# T3HornetV2.net
KiCad netlist of a schematic drawn in EAGLE
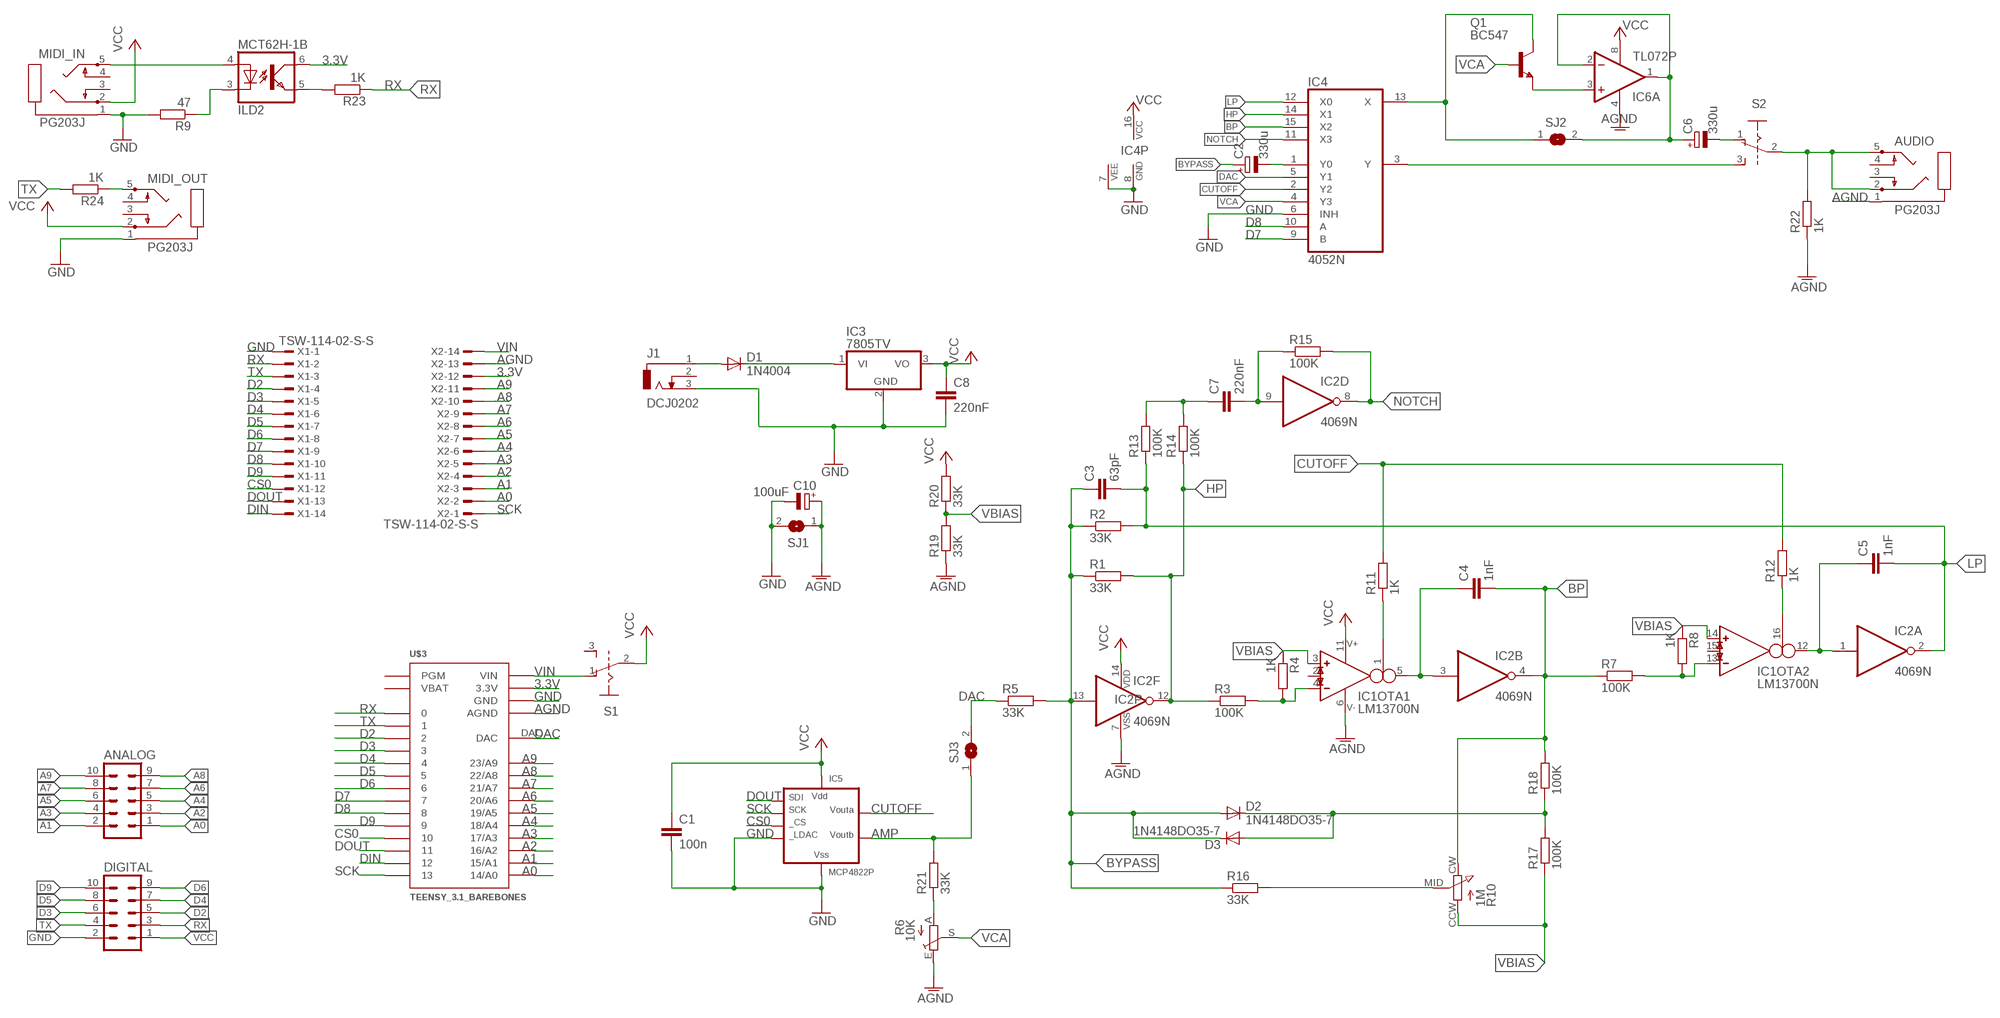
[diagram p0: schematic, sheet 1]

(export (version "E")
  (design (tool "Eeschema 10.0.6"))
  (components
    (comp (ref "ANALOG")
      (value "ML10")
      (footprint "eagle-import:ML10")
      (libsource (lib "eagle-import") (part "ML10"))
    )
    (comp (ref "AUDIO")
      (value "PG203J")
      (footprint "eagle-import:PG203J")
      (libsource (lib "eagle-import") (part "PG203J"))
    )
    (comp (ref "C1")
      (value "100n")
      (footprint "eagle-import:C050-030X075")
      (libsource (lib "eagle-import") (part "C-EU050-030X075"))
    )
    (comp (ref "C2")
      (value "330u")
      (footprint "eagle-import:E2,5-7")
      (libsource (lib "eagle-import") (part "CPOL-EUE2.5-7"))
    )
    (comp (ref "C3")
      (value "63pF")
      (footprint "eagle-import:C025-024X044")
      (libsource (lib "eagle-import") (part "C-EU025-024X044"))
    )
    (comp (ref "C4")
      (value "1nF")
      (footprint "eagle-import:C025-024X044")
      (libsource (lib "eagle-import") (part "C-EU025-024X044"))
    )
    (comp (ref "C5")
      (value "1nF")
      (footprint "eagle-import:C025-024X044")
      (libsource (lib "eagle-import") (part "C-EU025-024X044"))
    )
    (comp (ref "C6")
      (value "330u")
      (footprint "eagle-import:E2,5-7")
      (libsource (lib "eagle-import") (part "CPOL-EUE2.5-7"))
    )
    (comp (ref "C7")
      (value "220nF")
      (footprint "eagle-import:C050-030X075")
      (libsource (lib "eagle-import") (part "C-EU050-030X075"))
    )
    (comp (ref "C8")
      (value "220nF")
      (footprint "eagle-import:C050-030X075")
      (libsource (lib "eagle-import") (part "C-EU050-030X075"))
    )
    (comp (ref "C10")
      (value "100uF")
      (footprint "eagle-import:E2,5-6")
      (libsource (lib "eagle-import") (part "CPOL-EUE2.5-6"))
    )
    (comp (ref "D1")
      (value "1N4004")
      (footprint "eagle-import:DO41-10")
      (libsource (lib "eagle-import") (part "1N4004"))
    )
    (comp (ref "D2")
      (value "1N4148DO35-7")
      (footprint "eagle-import:DO35-7")
      (libsource (lib "eagle-import") (part "1N4148DO35-7"))
    )
    (comp (ref "D3")
      (value "1N4148DO35-7")
      (footprint "eagle-import:DO35-7")
      (libsource (lib "eagle-import") (part "1N4148DO35-7"))
    )
    (comp (ref "DIGITAL")
      (value "ML10")
      (footprint "eagle-import:ML10")
      (libsource (lib "eagle-import") (part "ML10"))
    )
    (comp (ref "IC1")
      (value "LM13700N")
      (footprint "eagle-import:DIL16")
      (libsource (lib "eagle-import") (part "LM13700N"))
    )
    (comp (ref "IC2")
      (value "4069N")
      (footprint "eagle-import:DIL14")
      (libsource (lib "eagle-import") (part "4069N"))
    )
    (comp (ref "IC3")
      (value "7805TV")
      (footprint "eagle-import:TO220V")
      (libsource (lib "eagle-import") (part "78TV05"))
    )
    (comp (ref "IC4")
      (value "4052N")
      (footprint "eagle-import:DIL16")
      (libsource (lib "eagle-import") (part "4052N"))
    )
    (comp (ref "IC5")
      (value "MCP4822P")
      (footprint "eagle-import:DIL8")
      (libsource (lib "eagle-import") (part "MCP4822P"))
    )
    (comp (ref "IC6")
      (value "TL072P")
      (footprint "eagle-import:DIL08")
      (libsource (lib "eagle-import") (part "TL072P"))
    )
    (comp (ref "J1")
      (value "DCJ0202")
      (footprint "eagle-import:DCJ0202")
      (libsource (lib "eagle-import") (part "DCJ0202"))
    )
    (comp (ref "MCT62H-1")
      (value "ILD2")
      (footprint "eagle-import:DIL08")
      (libsource (lib "eagle-import") (part "ILD2"))
    )
    (comp (ref "MIDI_IN")
      (value "PG203J")
      (footprint "eagle-import:PG203J")
      (libsource (lib "eagle-import") (part "PG203J"))
    )
    (comp (ref "MIDI_OUT")
      (value "PG203J")
      (footprint "eagle-import:PG203J")
      (libsource (lib "eagle-import") (part "PG203J"))
    )
    (comp (ref "Q1")
      (value "BC547")
      (footprint "eagle-import:TO92")
      (libsource (lib "eagle-import") (part "BC547"))
    )
    (comp (ref "R1")
      (value "33K")
      (footprint "eagle-import:0207_7")
      (libsource (lib "eagle-import") (part "R-EU_0207/7"))
    )
    (comp (ref "R2")
      (value "33K")
      (footprint "eagle-import:0207_7")
      (libsource (lib "eagle-import") (part "R-EU_0207/7"))
    )
    (comp (ref "R3")
      (value "100K")
      (footprint "eagle-import:0207_7")
      (libsource (lib "eagle-import") (part "R-EU_0207/7"))
    )
    (comp (ref "R4")
      (value "1K")
      (footprint "eagle-import:0207_7")
      (libsource (lib "eagle-import") (part "R-EU_0207/7"))
    )
    (comp (ref "R5")
      (value "33K")
      (footprint "eagle-import:0207_7")
      (libsource (lib "eagle-import") (part "R-EU_0207/7"))
    )
    (comp (ref "R6")
      (value "10K")
      (footprint "eagle-import:CA9V")
      (libsource (lib "eagle-import") (part "TRIM_EU-CA9V"))
    )
    (comp (ref "R7")
      (value "100K")
      (footprint "eagle-import:0207_7")
      (libsource (lib "eagle-import") (part "R-EU_0207/7"))
    )
    (comp (ref "R8")
      (value "1K")
      (footprint "eagle-import:0207_7")
      (libsource (lib "eagle-import") (part "R-EU_0207/7"))
    )
    (comp (ref "R9")
      (value "47")
      (footprint "eagle-import:0207_7")
      (libsource (lib "eagle-import") (part "R-EU_0207/7"))
    )
    (comp (ref "R10")
      (value "1M")
      (footprint "eagle-import:P120PK")
      (libsource (lib "eagle-import") (part "P120PK"))
    )
    (comp (ref "R11")
      (value "1K")
      (footprint "eagle-import:0207_7")
      (libsource (lib "eagle-import") (part "R-EU_0207/7"))
    )
    (comp (ref "R12")
      (value "1K")
      (footprint "eagle-import:0207_7")
      (libsource (lib "eagle-import") (part "R-EU_0207/7"))
    )
    (comp (ref "R13")
      (value "100K")
      (footprint "eagle-import:0207_7")
      (libsource (lib "eagle-import") (part "R-EU_0207/7"))
    )
    (comp (ref "R14")
      (value "100K")
      (footprint "eagle-import:0207_7")
      (libsource (lib "eagle-import") (part "R-EU_0207/7"))
    )
    (comp (ref "R15")
      (value "100K")
      (footprint "eagle-import:0207_7")
      (libsource (lib "eagle-import") (part "R-EU_0207/7"))
    )
    (comp (ref "R16")
      (value "33K")
      (footprint "eagle-import:0207_7")
      (libsource (lib "eagle-import") (part "R-EU_0207/7"))
    )
    (comp (ref "R17")
      (value "100K")
      (footprint "eagle-import:0207_7")
      (libsource (lib "eagle-import") (part "R-EU_0207/7"))
    )
    (comp (ref "R18")
      (value "100K")
      (footprint "eagle-import:0207_7")
      (libsource (lib "eagle-import") (part "R-EU_0207/7"))
    )
    (comp (ref "R19")
      (value "33K")
      (footprint "eagle-import:0207_7")
      (libsource (lib "eagle-import") (part "R-EU_0207/7"))
    )
    (comp (ref "R20")
      (value "33K")
      (footprint "eagle-import:0207_7")
      (libsource (lib "eagle-import") (part "R-EU_0207/7"))
    )
    (comp (ref "R21")
      (value "33K")
      (footprint "eagle-import:0207_7")
      (libsource (lib "eagle-import") (part "R-EU_0207/7"))
    )
    (comp (ref "R22")
      (value "1K")
      (footprint "eagle-import:0207_7")
      (libsource (lib "eagle-import") (part "R-EU_0207/7"))
    )
    (comp (ref "R23")
      (value "1K")
      (footprint "eagle-import:0207_7")
      (libsource (lib "eagle-import") (part "R-EU_0207/7"))
    )
    (comp (ref "R24")
      (value "1K")
      (footprint "eagle-import:0207_7")
      (libsource (lib "eagle-import") (part "R-EU_0207/7"))
    )
    (comp (ref "S1")
      (value "EG1218")
      (footprint "eagle-import:GF-126-0159")
      (libsource (lib "eagle-import") (part "EG1218"))
    )
    (comp (ref "S2")
      (value "EG1218")
      (footprint "eagle-import:GF-126-0159")
      (libsource (lib "eagle-import") (part "EG1218"))
    )
    (comp (ref "SJ1") (value "SJ") (footprint "eagle-import:SJ") (libsource (lib "eagle-import") (part "SJ")))
    (comp (ref "SJ2") (value "SJ") (footprint "eagle-import:SJ") (libsource (lib "eagle-import") (part "SJ")))
    (comp (ref "SJ3") (value "SJ") (footprint "eagle-import:SJ") (libsource (lib "eagle-import") (part "SJ")))
    (comp (ref "U$3")
      (value "TEENSY_3.1_BAREBONES")
      (footprint "eagle-import:TEENSY_3.1_BAREBONES")
      (libsource (lib "eagle-import") (part "TEENSY_3.1_BAREBONES"))
    )
    (comp (ref "X1")
      (value "TSW-114-02-S-S")
      (footprint "eagle-import:TSW-114-02-S-S")
      (libsource (lib "eagle-import") (part "TSW-114-02-S-S"))
    )
    (comp (ref "X2")
      (value "TSW-114-02-S-S")
      (footprint "eagle-import:TSW-114-02-S-S")
      (libsource (lib "eagle-import") (part "TSW-114-02-S-S"))
    )
  )
  (nets
    (net (code "1") (name "/3.3V") (class "Default")
      (node (ref "MCT62H-1") (pin "6") (pinfunction "COL_6") (pintype "passive"))
      (node (ref "U$3") (pin "3.3V1") (pinfunction "3.3V_3.3V1") (pintype "power_in"))
      (node (ref "U$3") (pin "3.3V2") (pinfunction "3.3V_3.3V2") (pintype "power_in"))
      (node (ref "X2") (pin "12") (pinfunction "1_12") (pintype "passive"))
    )
    (net (code "2") (name "/AMP") (class "Default")
      (node (ref "IC5") (pin "6") (pinfunction "VOUTB_6") (pintype "output"))
      (node (ref "R21") (pin "2") (pinfunction "2_2") (pintype "passive"))
      (node (ref "SJ3") (pin "1") (pinfunction "1_1") (pintype "passive"))
    )
    (net (code "3") (name "/CS0") (class "Default")
      (node (ref "IC5") (pin "2") (pinfunction "CS_2") (pintype "input"))
      (node (ref "U$3") (pin "10") (pinfunction "10_10") (pintype "bidirectional"))
      (node (ref "X1") (pin "12") (pinfunction "1_12") (pintype "passive"))
    )
    (net (code "4") (name "/D7") (class "Default")
      (node (ref "IC4") (pin "9") (pinfunction "B_9") (pintype "input"))
      (node (ref "U$3") (pin "7") (pinfunction "7_7") (pintype "bidirectional"))
      (node (ref "X1") (pin "9") (pinfunction "1_9") (pintype "passive"))
    )
    (net (code "5") (name "/D8") (class "Default")
      (node (ref "IC4") (pin "10") (pinfunction "A_10") (pintype "input"))
      (node (ref "U$3") (pin "8") (pinfunction "8_8") (pintype "bidirectional"))
      (node (ref "X1") (pin "10") (pinfunction "1_10") (pintype "passive"))
    )
    (net (code "6") (name "/DIN") (class "Default")
      (node (ref "U$3") (pin "12") (pinfunction "12_12") (pintype "bidirectional"))
      (node (ref "X1") (pin "14") (pinfunction "1_14") (pintype "passive"))
    )
    (net (code "7") (name "/DOUT") (class "Default")
      (node (ref "IC5") (pin "4") (pinfunction "SDI_4") (pintype "input"))
      (node (ref "U$3") (pin "11") (pinfunction "11_11") (pintype "bidirectional"))
      (node (ref "X1") (pin "13") (pinfunction "1_13") (pintype "passive"))
    )
    (net (code "8") (name "/SCK") (class "Default")
      (node (ref "IC5") (pin "3") (pinfunction "SCK_3") (pintype "input"))
      (node (ref "U$3") (pin "13") (pinfunction "13_13") (pintype "bidirectional"))
      (node (ref "X2") (pin "1") (pinfunction "1_1") (pintype "passive"))
    )
    (net (code "9") (name "/VBAT") (class "Default")
      (node (ref "U$3") (pin "VBAT") (pinfunction "VBAT_VBAT") (pintype "power_in"))
    )
    (net (code "10") (name "/VIN") (class "Default")
      (node (ref "S1") (pin "1") (pinfunction "1_1") (pintype "passive"))
      (node (ref "U$3") (pin "VIN") (pinfunction "VIN_VIN") (pintype "power_in"))
      (node (ref "X2") (pin "14") (pinfunction "1_14") (pintype "passive"))
    )
    (net (code "11") (name "A0") (class "Default")
      (node (ref "ANALOG") (pin "1") (pinfunction "1_1") (pintype "passive"))
      (node (ref "U$3") (pin "14/A0") (pinfunction "14/A0_14/A0") (pintype "bidirectional"))
      (node (ref "X2") (pin "2") (pinfunction "1_2") (pintype "passive"))
    )
    (net (code "12") (name "A1") (class "Default")
      (node (ref "ANALOG") (pin "2") (pinfunction "2_2") (pintype "passive"))
      (node (ref "U$3") (pin "15/A1") (pinfunction "15/A1_15/A1") (pintype "bidirectional"))
      (node (ref "X2") (pin "3") (pinfunction "1_3") (pintype "passive"))
    )
    (net (code "13") (name "A2") (class "Default")
      (node (ref "ANALOG") (pin "3") (pinfunction "3_3") (pintype "passive"))
      (node (ref "U$3") (pin "16/A2") (pinfunction "16/A2_16/A2") (pintype "bidirectional"))
      (node (ref "X2") (pin "4") (pinfunction "1_4") (pintype "passive"))
    )
    (net (code "14") (name "A3") (class "Default")
      (node (ref "ANALOG") (pin "4") (pinfunction "4_4") (pintype "passive"))
      (node (ref "U$3") (pin "17/A3") (pinfunction "17/A3_17/A3") (pintype "bidirectional"))
      (node (ref "X2") (pin "5") (pinfunction "1_5") (pintype "passive"))
    )
    (net (code "15") (name "A4") (class "Default")
      (node (ref "ANALOG") (pin "5") (pinfunction "5_5") (pintype "passive"))
      (node (ref "U$3") (pin "18/A4") (pinfunction "18/A4_18/A4") (pintype "bidirectional"))
      (node (ref "X2") (pin "6") (pinfunction "1_6") (pintype "passive"))
    )
    (net (code "16") (name "A5") (class "Default")
      (node (ref "ANALOG") (pin "6") (pinfunction "6_6") (pintype "passive"))
      (node (ref "U$3") (pin "19/A5") (pinfunction "19/A5_19/A5") (pintype "bidirectional"))
      (node (ref "X2") (pin "7") (pinfunction "1_7") (pintype "passive"))
    )
    (net (code "17") (name "A6") (class "Default")
      (node (ref "ANALOG") (pin "7") (pinfunction "7_7") (pintype "passive"))
      (node (ref "U$3") (pin "20/A6") (pinfunction "20/A6_20/A6") (pintype "bidirectional"))
      (node (ref "X2") (pin "8") (pinfunction "1_8") (pintype "passive"))
    )
    (net (code "18") (name "A7") (class "Default")
      (node (ref "ANALOG") (pin "8") (pinfunction "8_8") (pintype "passive"))
      (node (ref "U$3") (pin "21/A7") (pinfunction "21/A7_21/A7") (pintype "bidirectional"))
      (node (ref "X2") (pin "9") (pinfunction "1_9") (pintype "passive"))
    )
    (net (code "19") (name "A8") (class "Default")
      (node (ref "ANALOG") (pin "9") (pinfunction "9_9") (pintype "passive"))
      (node (ref "U$3") (pin "22/A8") (pinfunction "22/A8_22/A8") (pintype "bidirectional"))
      (node (ref "X2") (pin "10") (pinfunction "1_10") (pintype "passive"))
    )
    (net (code "20") (name "A9") (class "Default")
      (node (ref "ANALOG") (pin "10") (pinfunction "10_10") (pintype "passive"))
      (node (ref "U$3") (pin "23/A9") (pinfunction "23/A9_23/A9") (pintype "bidirectional"))
      (node (ref "X2") (pin "11") (pinfunction "1_11") (pintype "passive"))
    )
    (net (code "21") (name "AGND") (class "Default")
      (node (ref "AUDIO") (pin "1") (pinfunction "1_1") (pintype "passive"))
      (node (ref "C10") (pin "+") (pinfunction "+_+") (pintype "passive"))
      (node (ref "IC1") (pin "6") (pinfunction "V-_6") (pintype "power_in"))
      (node (ref "IC2") (pin "7") (pinfunction "VSS_7") (pintype "power_in"))
      (node (ref "IC6") (pin "4") (pinfunction "V-_4") (pintype "power_in"))
      (node (ref "R19") (pin "1") (pinfunction "1_1") (pintype "passive"))
      (node (ref "R22") (pin "1") (pinfunction "1_1") (pintype "passive"))
      (node (ref "R6") (pin "E") (pinfunction "E_E") (pintype "passive"))
      (node (ref "SJ1") (pin "1") (pinfunction "1_1") (pintype "passive"))
      (node (ref "U$3") (pin "AGND") (pinfunction "AGND_AGND") (pintype "power_in"))
      (node (ref "X2") (pin "13") (pinfunction "1_13") (pintype "passive"))
    )
    (net (code "22") (name "BP") (class "Default")
      (node (ref "C4") (pin "2") (pinfunction "2_2") (pintype "passive"))
      (node (ref "IC2") (pin "4") (pinfunction "O_4") (pintype "output"))
      (node (ref "IC4") (pin "15") (pinfunction "X2_15") (pintype "bidirectional"))
      (node (ref "R10") (pin "CW") (pinfunction "CW_CW") (pintype "passive"))
      (node (ref "R18") (pin "2") (pinfunction "2_2") (pintype "passive"))
      (node (ref "R7") (pin "1") (pinfunction "1_1") (pintype "passive"))
    )
    (net (code "23") (name "BYPASS") (class "Default")
      (node (ref "C2") (pin "+") (pinfunction "+_+") (pintype "passive"))
      (node (ref "C3") (pin "1") (pinfunction "1_1") (pintype "passive"))
      (node (ref "D2") (pin "A") (pinfunction "A_A") (pintype "passive"))
      (node (ref "D3") (pin "C") (pinfunction "C_C") (pintype "passive"))
      (node (ref "IC2") (pin "13") (pinfunction "I_13") (pintype "input"))
      (node (ref "R1") (pin "1") (pinfunction "1_1") (pintype "passive"))
      (node (ref "R16") (pin "1") (pinfunction "1_1") (pintype "passive"))
      (node (ref "R2") (pin "1") (pinfunction "1_1") (pintype "passive"))
      (node (ref "R5") (pin "2") (pinfunction "2_2") (pintype "passive"))
    )
    (net (code "24") (name "CUTOFF") (class "Default")
      (node (ref "IC4") (pin "2") (pinfunction "Y2_2") (pintype "bidirectional"))
      (node (ref "IC5") (pin "8") (pinfunction "VOUTA_8") (pintype "output"))
      (node (ref "R11") (pin "2") (pinfunction "2_2") (pintype "passive"))
      (node (ref "R12") (pin "2") (pinfunction "2_2") (pintype "passive"))
    )
    (net (code "25") (name "D2") (class "Default")
      (node (ref "DIGITAL") (pin "5") (pinfunction "5_5") (pintype "passive"))
      (node (ref "U$3") (pin "2") (pinfunction "2_2") (pintype "bidirectional"))
      (node (ref "X1") (pin "4") (pinfunction "1_4") (pintype "passive"))
    )
    (net (code "26") (name "D3") (class "Default")
      (node (ref "DIGITAL") (pin "6") (pinfunction "6_6") (pintype "passive"))
      (node (ref "U$3") (pin "3") (pinfunction "3_3") (pintype "bidirectional"))
      (node (ref "X1") (pin "5") (pinfunction "1_5") (pintype "passive"))
    )
    (net (code "27") (name "D4") (class "Default")
      (node (ref "DIGITAL") (pin "7") (pinfunction "7_7") (pintype "passive"))
      (node (ref "U$3") (pin "4") (pinfunction "4_4") (pintype "bidirectional"))
      (node (ref "X1") (pin "6") (pinfunction "1_6") (pintype "passive"))
    )
    (net (code "28") (name "D5") (class "Default")
      (node (ref "DIGITAL") (pin "8") (pinfunction "8_8") (pintype "passive"))
      (node (ref "U$3") (pin "5") (pinfunction "5_5") (pintype "bidirectional"))
      (node (ref "X1") (pin "7") (pinfunction "1_7") (pintype "passive"))
    )
    (net (code "29") (name "D6") (class "Default")
      (node (ref "DIGITAL") (pin "9") (pinfunction "9_9") (pintype "passive"))
      (node (ref "U$3") (pin "6") (pinfunction "6_6") (pintype "bidirectional"))
      (node (ref "X1") (pin "8") (pinfunction "1_8") (pintype "passive"))
    )
    (net (code "30") (name "D9") (class "Default")
      (node (ref "DIGITAL") (pin "10") (pinfunction "10_10") (pintype "passive"))
      (node (ref "U$3") (pin "9") (pinfunction "9_9") (pintype "bidirectional"))
      (node (ref "X1") (pin "11") (pinfunction "1_11") (pintype "passive"))
    )
    (net (code "31") (name "DAC") (class "Default")
      (node (ref "IC4") (pin "5") (pinfunction "Y1_5") (pintype "bidirectional"))
      (node (ref "R5") (pin "1") (pinfunction "1_1") (pintype "passive"))
      (node (ref "SJ3") (pin "2") (pinfunction "2_2") (pintype "passive"))
      (node (ref "U$3") (pin "DAC") (pinfunction "DAC_DAC") (pintype "bidirectional"))
    )
    (net (code "32") (name "GND") (class "Default")
      (node (ref "C1") (pin "2") (pinfunction "2_2") (pintype "passive"))
      (node (ref "C10") (pin "-") (pinfunction "-_-") (pintype "passive"))
      (node (ref "C8") (pin "2") (pinfunction "2_2") (pintype "passive"))
      (node (ref "DIGITAL") (pin "2") (pinfunction "2_2") (pintype "passive"))
      (node (ref "IC3") (pin "2") (pinfunction "GND_2") (pintype "passive"))
      (node (ref "IC4") (pin "6") (pinfunction "INH_6") (pintype "input"))
      (node (ref "IC4") (pin "7") (pinfunction "VEE_7") (pintype "power_in"))
      (node (ref "IC4") (pin "8") (pinfunction "GND_8") (pintype "power_in"))
      (node (ref "IC5") (pin "5") (pinfunction "LDAC_5") (pintype "input"))
      (node (ref "IC5") (pin "7") (pinfunction "VSS_7") (pintype "power_in"))
      (node (ref "J1") (pin "3") (pinfunction "3_3") (pintype "passive"))
      (node (ref "MIDI_IN") (pin "1") (pinfunction "1_1") (pintype "passive"))
      (node (ref "MIDI_OUT") (pin "1") (pinfunction "1_1") (pintype "passive"))
      (node (ref "R9") (pin "2") (pinfunction "2_2") (pintype "passive"))
      (node (ref "SJ1") (pin "2") (pinfunction "2_2") (pintype "passive"))
      (node (ref "U$3") (pin "GND1") (pinfunction "GND_GND1") (pintype "power_in"))
      (node (ref "U$3") (pin "GND2") (pinfunction "GND_GND2") (pintype "power_in"))
      (node (ref "X1") (pin "1") (pinfunction "1_1") (pintype "passive"))
    )
    (net (code "33") (name "HP") (class "Default")
      (node (ref "IC2") (pin "12") (pinfunction "O_12") (pintype "output"))
      (node (ref "IC4") (pin "14") (pinfunction "X1_14") (pintype "bidirectional"))
      (node (ref "R1") (pin "2") (pinfunction "2_2") (pintype "passive"))
      (node (ref "R14") (pin "1") (pinfunction "1_1") (pintype "passive"))
      (node (ref "R3") (pin "1") (pinfunction "1_1") (pintype "passive"))
    )
    (net (code "34") (name "LP") (class "Default")
      (node (ref "C3") (pin "2") (pinfunction "2_2") (pintype "passive"))
      (node (ref "C5") (pin "2") (pinfunction "2_2") (pintype "passive"))
      (node (ref "IC2") (pin "2") (pinfunction "O_2") (pintype "output"))
      (node (ref "IC4") (pin "12") (pinfunction "X0_12") (pintype "bidirectional"))
      (node (ref "R13") (pin "1") (pinfunction "1_1") (pintype "passive"))
      (node (ref "R2") (pin "2") (pinfunction "2_2") (pintype "passive"))
    )
    (net (code "35") (name "NOTCH") (class "Default")
      (node (ref "IC2") (pin "8") (pinfunction "O_8") (pintype "output"))
      (node (ref "IC4") (pin "11") (pinfunction "X3_11") (pintype "bidirectional"))
      (node (ref "R15") (pin "2") (pinfunction "2_2") (pintype "passive"))
    )
    (net (code "36") (name "Net-(C6-Pad-)") (class "Default")
      (node (ref "C6") (pin "-") (pinfunction "-_-") (pintype "passive"))
      (node (ref "S2") (pin "1") (pinfunction "1_1") (pintype "passive"))
    )
    (net (code "37") (name "Net-(C7-Pad1)") (class "Default")
      (node (ref "C7") (pin "1") (pinfunction "1_1") (pintype "passive"))
      (node (ref "R13") (pin "2") (pinfunction "2_2") (pintype "passive"))
      (node (ref "R14") (pin "2") (pinfunction "2_2") (pintype "passive"))
    )
    (net (code "38") (name "Net-(D1-PadA)") (class "Default")
      (node (ref "D1") (pin "A") (pinfunction "A_A") (pintype "passive"))
      (node (ref "J1") (pin "1") (pinfunction "1_1") (pintype "passive"))
    )
    (net (code "39") (name "Net-(D2-PadC)") (class "Default")
      (node (ref "D2") (pin "C") (pinfunction "C_C") (pintype "passive"))
      (node (ref "D3") (pin "A") (pinfunction "A_A") (pintype "passive"))
      (node (ref "R17") (pin "2") (pinfunction "2_2") (pintype "passive"))
      (node (ref "R18") (pin "1") (pinfunction "1_1") (pintype "passive"))
    )
    (net (code "40") (name "Net-(IC1C-IN_N)") (class "Default")
      (node (ref "IC1") (pin "4") (pinfunction "IN_N_4") (pintype "input"))
      (node (ref "R3") (pin "2") (pinfunction "2_2") (pintype "passive"))
      (node (ref "R4") (pin "2") (pinfunction "2_2") (pintype "passive"))
    )
    (net (code "41") (name "Net-(IC1C-I_BIAS)") (class "Default")
      (node (ref "IC1") (pin "1") (pinfunction "I_BIAS_1") (pintype "input"))
      (node (ref "R11") (pin "1") (pinfunction "1_1") (pintype "passive"))
    )
    (net (code "42") (name "Net-(IC1C-OUT)") (class "Default")
      (node (ref "C4") (pin "1") (pinfunction "1_1") (pintype "passive"))
      (node (ref "IC1") (pin "5") (pinfunction "OUT_5") (pintype "output"))
      (node (ref "IC2") (pin "3") (pinfunction "I_3") (pintype "input"))
    )
    (net (code "43") (name "Net-(IC1D-IN_N)") (class "Default")
      (node (ref "IC1") (pin "13") (pinfunction "IN_N_13") (pintype "input"))
      (node (ref "R7") (pin "2") (pinfunction "2_2") (pintype "passive"))
      (node (ref "R8") (pin "2") (pinfunction "2_2") (pintype "passive"))
    )
    (net (code "44") (name "Net-(IC1D-I_BIAS)") (class "Default")
      (node (ref "IC1") (pin "16") (pinfunction "I_BIAS_16") (pintype "input"))
      (node (ref "R12") (pin "1") (pinfunction "1_1") (pintype "passive"))
    )
    (net (code "45") (name "Net-(IC1D-OUT)") (class "Default")
      (node (ref "C5") (pin "1") (pinfunction "1_1") (pintype "passive"))
      (node (ref "IC1") (pin "12") (pinfunction "OUT_12") (pintype "output"))
      (node (ref "IC2") (pin "1") (pinfunction "I_1") (pintype "input"))
    )
    (net (code "46") (name "Net-(IC2D-I)") (class "Default")
      (node (ref "C7") (pin "2") (pinfunction "2_2") (pintype "passive"))
      (node (ref "IC2") (pin "9") (pinfunction "I_9") (pintype "input"))
      (node (ref "R15") (pin "1") (pinfunction "1_1") (pintype "passive"))
    )
    (net (code "47") (name "Net-(IC3-VI)") (class "Default")
      (node (ref "D1") (pin "C") (pinfunction "C_C") (pintype "passive"))
      (node (ref "IC3") (pin "1") (pinfunction "VI_1") (pintype "input"))
    )
    (net (code "48") (name "Net-(IC4A-X)") (class "Default")
      (node (ref "IC4") (pin "13") (pinfunction "X_13") (pintype "bidirectional"))
      (node (ref "Q1") (pin "3") (pinfunction "C_3") (pintype "passive"))
      (node (ref "SJ2") (pin "1") (pinfunction "1_1") (pintype "passive"))
    )
    (net (code "49") (name "Net-(IC4A-Y)") (class "Default")
      (node (ref "IC4") (pin "3") (pinfunction "Y_3") (pintype "bidirectional"))
      (node (ref "S2") (pin "3") (pinfunction "3_3") (pintype "passive"))
    )
    (net (code "50") (name "Net-(IC4A-Y0)") (class "Default")
      (node (ref "C2") (pin "-") (pinfunction "-_-") (pintype "passive"))
      (node (ref "IC4") (pin "1") (pinfunction "Y0_1") (pintype "bidirectional"))
    )
    (net (code "51") (name "Net-(IC6A-+IN)") (class "Default")
      (node (ref "IC6") (pin "3") (pinfunction "+IN_3") (pintype "input"))
      (node (ref "Q1") (pin "1") (pinfunction "E_1") (pintype "passive"))
    )
    (net (code "52") (name "Net-(IC6A--IN)") (class "Default")
      (node (ref "C6") (pin "+") (pinfunction "+_+") (pintype "passive"))
      (node (ref "IC6") (pin "1") (pinfunction "OUT_1") (pintype "output"))
      (node (ref "IC6") (pin "2") (pinfunction "-IN_2") (pintype "input"))
      (node (ref "SJ2") (pin "2") (pinfunction "2_2") (pintype "passive"))
    )
    (net (code "53") (name "Net-(MCT62H-1B-A)") (class "Default")
      (node (ref "MCT62H-1") (pin "4") (pinfunction "A_4") (pintype "passive"))
      (node (ref "MIDI_IN") (pin "5") (pinfunction "5_5") (pintype "passive"))
    )
    (net (code "54") (name "Net-(MCT62H-1B-C)") (class "Default")
      (node (ref "MCT62H-1") (pin "3") (pinfunction "C_3") (pintype "passive"))
      (node (ref "R9") (pin "1") (pinfunction "1_1") (pintype "passive"))
    )
    (net (code "55") (name "Net-(MCT62H-1B-EMIT)") (class "Default")
      (node (ref "MCT62H-1") (pin "5") (pinfunction "EMIT_5") (pintype "passive"))
      (node (ref "R23") (pin "2") (pinfunction "2_2") (pintype "passive"))
    )
    (net (code "56") (name "Net-(MIDI_OUT-Pad5)") (class "Default")
      (node (ref "MIDI_OUT") (pin "5") (pinfunction "5_5") (pintype "passive"))
      (node (ref "R24") (pin "1") (pinfunction "1_1") (pintype "passive"))
    )
    (net (code "57") (name "Net-(R10-PadMID)") (class "Default")
      (node (ref "R10") (pin "MID") (pinfunction "MID_MID") (pintype "passive"))
      (node (ref "R16") (pin "2") (pinfunction "2_2") (pintype "passive"))
    )
    (net (code "58") (name "Net-(R21-Pad1)") (class "Default")
      (node (ref "R21") (pin "1") (pinfunction "1_1") (pintype "passive"))
      (node (ref "R6") (pin "A") (pinfunction "A_A") (pintype "passive"))
    )
    (net (code "59") (name "Net-(S2-02)") (class "Default")
      (node (ref "AUDIO") (pin "2") (pinfunction "2_2") (pintype "passive"))
      (node (ref "AUDIO") (pin "5") (pinfunction "5_5") (pintype "passive"))
      (node (ref "R22") (pin "2") (pinfunction "2_2") (pintype "passive"))
      (node (ref "S2") (pin "2") (pinfunction "02_2") (pintype "passive"))
    )
    (net (code "60") (name "RX") (class "Default")
      (node (ref "DIGITAL") (pin "3") (pinfunction "3_3") (pintype "passive"))
      (node (ref "R23") (pin "1") (pinfunction "1_1") (pintype "passive"))
      (node (ref "U$3") (pin "0") (pinfunction "0_0") (pintype "bidirectional"))
      (node (ref "X1") (pin "2") (pinfunction "1_2") (pintype "passive"))
    )
    (net (code "61") (name "TX") (class "Default")
      (node (ref "DIGITAL") (pin "4") (pinfunction "4_4") (pintype "passive"))
      (node (ref "R24") (pin "2") (pinfunction "2_2") (pintype "passive"))
      (node (ref "U$3") (pin "1") (pinfunction "1_1") (pintype "bidirectional"))
      (node (ref "X1") (pin "3") (pinfunction "1_3") (pintype "passive"))
    )
    (net (code "62") (name "VBIAS") (class "Default")
      (node (ref "IC1") (pin "14") (pinfunction "IN_P_14") (pintype "input"))
      (node (ref "IC1") (pin "3") (pinfunction "IN_P_3") (pintype "input"))
      (node (ref "R10") (pin "CCW") (pinfunction "CCW_CCW") (pintype "passive"))
      (node (ref "R17") (pin "1") (pinfunction "1_1") (pintype "passive"))
      (node (ref "R19") (pin "2") (pinfunction "2_2") (pintype "passive"))
      (node (ref "R20") (pin "1") (pinfunction "1_1") (pintype "passive"))
      (node (ref "R4") (pin "1") (pinfunction "1_1") (pintype "passive"))
      (node (ref "R8") (pin "1") (pinfunction "1_1") (pintype "passive"))
    )
    (net (code "63") (name "VCA") (class "Default")
      (node (ref "IC4") (pin "4") (pinfunction "Y3_4") (pintype "bidirectional"))
      (node (ref "Q1") (pin "2") (pinfunction "B_2") (pintype "passive"))
      (node (ref "R6") (pin "S") (pinfunction "S_S") (pintype "passive"))
    )
    (net (code "64") (name "VCC") (class "Default")
      (node (ref "C1") (pin "1") (pinfunction "1_1") (pintype "passive"))
      (node (ref "C8") (pin "1") (pinfunction "1_1") (pintype "passive"))
      (node (ref "DIGITAL") (pin "1") (pinfunction "1_1") (pintype "passive"))
      (node (ref "IC1") (pin "11") (pinfunction "V+_11") (pintype "power_in"))
      (node (ref "IC2") (pin "14") (pinfunction "VDD_14") (pintype "power_in"))
      (node (ref "IC3") (pin "3") (pinfunction "VO_3") (pintype "passive"))
      (node (ref "IC4") (pin "16") (pinfunction "VCC_16") (pintype "power_in"))
      (node (ref "IC5") (pin "1") (pinfunction "VDD_1") (pintype "power_in"))
      (node (ref "IC6") (pin "8") (pinfunction "V+_8") (pintype "power_in"))
      (node (ref "MIDI_IN") (pin "2") (pinfunction "2_2") (pintype "passive"))
      (node (ref "MIDI_OUT") (pin "2") (pinfunction "2_2") (pintype "passive"))
      (node (ref "R20") (pin "2") (pinfunction "2_2") (pintype "passive"))
      (node (ref "S1") (pin "2") (pinfunction "02_2") (pintype "passive"))
    )
    (net (code "65") (name "unconnected-(AUDIO-Pad3)") (class "Default")
      (node (ref "AUDIO") (pin "3") (pinfunction "3_3") (pintype "passive"))
    )
    (net (code "66") (name "unconnected-(AUDIO-Pad4)") (class "Default")
      (node (ref "AUDIO") (pin "4") (pinfunction "4_4") (pintype "passive"))
    )
    (net (code "67") (name "unconnected-(IC1C-I_DIODE-Pad2)") (class "Default")
      (node (ref "IC1") (pin "2") (pinfunction "I_DIODE_2") (pintype "input"))
    )
    (net (code "68") (name "unconnected-(IC1D-I_DIODE-Pad15)") (class "Default")
      (node (ref "IC1") (pin "15") (pinfunction "I_DIODE_15") (pintype "input"))
    )
    (net (code "69") (name "unconnected-(J1-Pad2)") (class "Default")
      (node (ref "J1") (pin "2") (pinfunction "2_2") (pintype "passive"))
    )
    (net (code "70") (name "unconnected-(MIDI_IN-Pad3)") (class "Default")
      (node (ref "MIDI_IN") (pin "3") (pinfunction "3_3") (pintype "passive"))
    )
    (net (code "71") (name "unconnected-(MIDI_IN-Pad4)") (class "Default")
      (node (ref "MIDI_IN") (pin "4") (pinfunction "4_4") (pintype "passive"))
    )
    (net (code "72") (name "unconnected-(MIDI_OUT-Pad3)") (class "Default")
      (node (ref "MIDI_OUT") (pin "3") (pinfunction "3_3") (pintype "passive"))
    )
    (net (code "73") (name "unconnected-(MIDI_OUT-Pad4)") (class "Default")
      (node (ref "MIDI_OUT") (pin "4") (pinfunction "4_4") (pintype "passive"))
    )
    (net (code "74") (name "unconnected-(S1-Pad3)") (class "Default")
      (node (ref "S1") (pin "3") (pinfunction "3_3") (pintype "passive"))
    )
    (net (code "75") (name "unconnected-(U$3-PadPGM)") (class "Default")
      (node (ref "U$3") (pin "PGM") (pinfunction "PGM_PGM") (pintype "input"))
    )
  )
)
